# BuckConverter.net
KiCad netlist of a schematic drawn in Altium Designer
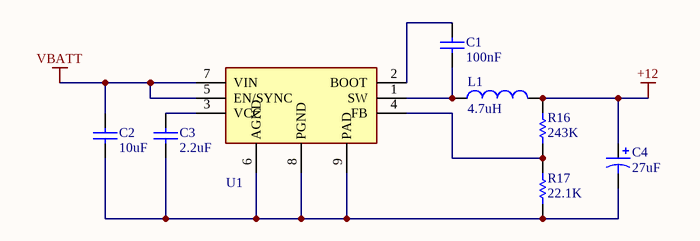
[diagram p0: BuckConverter.SchDoc]

(export (version "E")
  (design (tool "Eeschema 10.0.6"))
  (components
    (comp (ref "C1")
      (value "100nF")
      (footprint "0603 - Capacitor")
      (description "Nonpolarized Capacitor")
      (fields (field (name "Comment") "Capacitor - Nonpolarized"))
      (libsource (lib "General") (part "Capacitor - Nonpolarized"))
    )
    (comp (ref "C2")
      (value "10uF")
      (footprint "0603 - Capacitor")
      (description "Nonpolarized Capacitor")
      (fields (field (name "Comment") "Capacitor - Nonpolarized"))
      (libsource (lib "General") (part "Capacitor - Nonpolarized"))
    )
    (comp (ref "C3")
      (value "2.2uF")
      (footprint "0603 - Capacitor")
      (description "Nonpolarized Capacitor")
      (fields (field (name "Comment") "Capacitor - Nonpolarized"))
      (libsource (lib "General") (part "Capacitor - Nonpolarized"))
    )
    (comp (ref "C4")
      (value "27uF")
      (footprint "OCVZ0606 - CAPACITOR")
      (description "Polarized Capacitor")
      (fields (field (name "Comment") "Capacitor - Polarized"))
      (libsource (lib "General") (part "Capacitor - Polarized"))
    )
    (comp (ref "L1")
      (value "4.7uH")
      (footprint "MSS1210 - INDUCTOR")
      (description "Inductor")
      (libsource (lib "General") (part "Inductor"))
    )
    (comp (ref "R16")
      (value "243K")
      (footprint "0603 - Resistor")
      (description "Resistor")
      (libsource (lib "General") (part "Resistor"))
    )
    (comp (ref "R17")
      (value "22.1K")
      (footprint "0603 - Resistor")
      (description "Resistor")
      (libsource (lib "General") (part "Resistor"))
    )
    (comp (ref "U1")
      (value "LMR23625CDDAR")
      (footprint "LMR23625CDDAR")
      (description "36V 2.5A Buck Converter")
      (fields (field (name "MANUFACTURER") "TI"))
      (libsource (lib "Embedded") (part "LMR23625CDDAR"))
    )
  )
  (nets
    (net (code "1") (name "+12") (class "Default")
      (node (ref "C4") (pin "1") (pinfunction "1_1") (pintype "passive"))
      (node (ref "L1") (pin "2") (pinfunction "2_2") (pintype "passive"))
      (node (ref "R16") (pin "2") (pinfunction "2_2") (pintype "passive"))
    )
    (net (code "2") (name "Net-(U1-AGND)") (class "Default")
      (node (ref "C2") (pin "1") (pinfunction "1_1") (pintype "passive"))
      (node (ref "C3") (pin "1") (pinfunction "1_1") (pintype "passive"))
      (node (ref "C4") (pin "2") (pinfunction "2_2") (pintype "passive"))
      (node (ref "R17") (pin "1") (pinfunction "1_1") (pintype "passive"))
      (node (ref "U1") (pin "6") (pinfunction "AGND_6") (pintype "passive"))
      (node (ref "U1") (pin "8") (pinfunction "PGND_8") (pintype "passive"))
      (node (ref "U1") (pin "9") (pinfunction "PAD_9") (pintype "passive"))
    )
    (net (code "3") (name "Net-(U1-BOOT)") (class "Default")
      (node (ref "C1") (pin "2") (pinfunction "2_2") (pintype "passive"))
      (node (ref "U1") (pin "2") (pinfunction "BOOT_2") (pintype "passive"))
    )
    (net (code "4") (name "Net-(U1-FB)") (class "Default")
      (node (ref "R16") (pin "1") (pinfunction "1_1") (pintype "passive"))
      (node (ref "R17") (pin "2") (pinfunction "2_2") (pintype "passive"))
      (node (ref "U1") (pin "4") (pinfunction "FB_4") (pintype "passive"))
    )
    (net (code "5") (name "Net-(U1-SW)") (class "Default")
      (node (ref "C1") (pin "1") (pinfunction "1_1") (pintype "passive"))
      (node (ref "L1") (pin "1") (pinfunction "1_1") (pintype "passive"))
      (node (ref "U1") (pin "1") (pinfunction "SW_1") (pintype "passive"))
    )
    (net (code "6") (name "Net-(U1-VCC)") (class "Default")
      (node (ref "C3") (pin "2") (pinfunction "2_2") (pintype "passive"))
      (node (ref "U1") (pin "3") (pinfunction "VCC_3") (pintype "passive"))
    )
    (net (code "7") (name "VBATT") (class "Default")
      (node (ref "C2") (pin "2") (pinfunction "2_2") (pintype "passive"))
      (node (ref "U1") (pin "5") (pinfunction "EN/SYNC_5") (pintype "passive"))
      (node (ref "U1") (pin "7") (pinfunction "VIN_7") (pintype "passive"))
    )
  )
)
